# prox_board_rotate.net
KiCad netlist of a schematic drawn in EAGLE
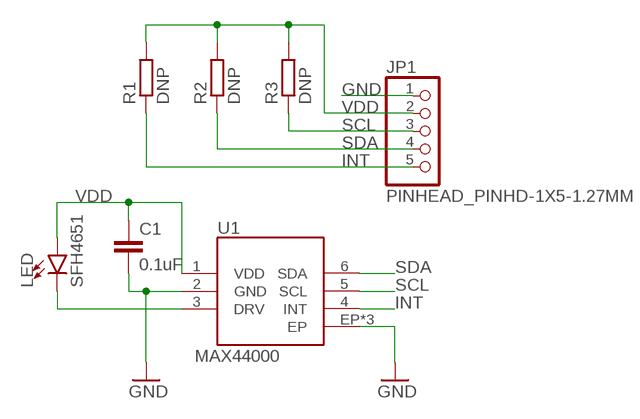
[diagram p0: schematic, sheet 1]

(export (version "E")
  (design (tool "Eeschema 10.0.6"))
  (components
    (comp (ref "C1")
      (value "0.1uF")
      (footprint "eagle-import:C0603")
      (libsource (lib "eagle-import") (part "C-EUC0603"))
    )
    (comp (ref "JP1")
      (value "PINHEAD_PINHD-1X5-1.27MM")
      (footprint "eagle-import:PINHEAD_1X05-1.27MM")
      (libsource (lib "eagle-import") (part "PINHEAD_PINHD-1X5-1.27MM"))
    )
    (comp (ref "LED")
      (value "SFH4651")
      (footprint "eagle-import:MIDLED")
      (libsource (lib "eagle-import") (part "SFH4651"))
    )
    (comp (ref "R1")
      (value "DNP")
      (footprint "eagle-import:R0603")
      (libsource (lib "eagle-import") (part "R-EU_R0603"))
    )
    (comp (ref "R2")
      (value "DNP")
      (footprint "eagle-import:R0603")
      (libsource (lib "eagle-import") (part "R-EU_R0603"))
    )
    (comp (ref "R3")
      (value "DNP")
      (footprint "eagle-import:R0603")
      (libsource (lib "eagle-import") (part "R-EU_R0603"))
    )
    (comp (ref "U1")
      (value "MAX44000")
      (footprint "eagle-import:6OTDFN-EP")
      (libsource (lib "eagle-import") (part "MAX44000"))
    )
  )
  (nets
    (net (code "1") (name "/INT") (class "Default")
      (node (ref "JP1") (pin "5") (pinfunction "5_5") (pintype "passive"))
      (node (ref "R1") (pin "1") (pinfunction "1_1") (pintype "passive"))
      (node (ref "U1") (pin "4") (pinfunction "INT_4") (pintype "bidirectional"))
    )
    (net (code "2") (name "/SCL") (class "Default")
      (node (ref "JP1") (pin "3") (pinfunction "3_3") (pintype "passive"))
      (node (ref "R3") (pin "1") (pinfunction "1_1") (pintype "passive"))
      (node (ref "U1") (pin "5") (pinfunction "SCL_5") (pintype "bidirectional"))
    )
    (net (code "3") (name "/SDA") (class "Default")
      (node (ref "JP1") (pin "4") (pinfunction "4_4") (pintype "passive"))
      (node (ref "R2") (pin "1") (pinfunction "1_1") (pintype "passive"))
      (node (ref "U1") (pin "6") (pinfunction "SDA_6") (pintype "bidirectional"))
    )
    (net (code "4") (name "/VDD") (class "Default")
      (node (ref "C1") (pin "1") (pinfunction "1_1") (pintype "passive"))
      (node (ref "JP1") (pin "2") (pinfunction "2_2") (pintype "passive"))
      (node (ref "LED") (pin "A") (pinfunction "A_A") (pintype "passive"))
      (node (ref "R1") (pin "2") (pinfunction "2_2") (pintype "passive"))
      (node (ref "R2") (pin "2") (pinfunction "2_2") (pintype "passive"))
      (node (ref "R3") (pin "2") (pinfunction "2_2") (pintype "passive"))
      (node (ref "U1") (pin "1") (pinfunction "VDD_1") (pintype "bidirectional"))
    )
    (net (code "5") (name "GND") (class "Default")
      (node (ref "C1") (pin "2") (pinfunction "2_2") (pintype "passive"))
      (node (ref "JP1") (pin "1") (pinfunction "1_1") (pintype "passive"))
      (node (ref "U1") (pin "2") (pinfunction "GND_2") (pintype "bidirectional"))
      (node (ref "U1") (pin "EP") (pinfunction "EP_EP") (pintype "bidirectional"))
      (node (ref "U1") (pin "P$1") (pinfunction "EP_P$1") (pintype "bidirectional"))
      (node (ref "U1") (pin "P$2") (pinfunction "EP_P$2") (pintype "bidirectional"))
    )
    (net (code "6") (name "Net-(U1-DRV)") (class "Default")
      (node (ref "LED") (pin "C") (pinfunction "C_C") (pintype "passive"))
      (node (ref "U1") (pin "3") (pinfunction "DRV_3") (pintype "bidirectional"))
    )
  )
)
